# MPCBoard.net
KiCad netlist of a schematic drawn in Altium Designer
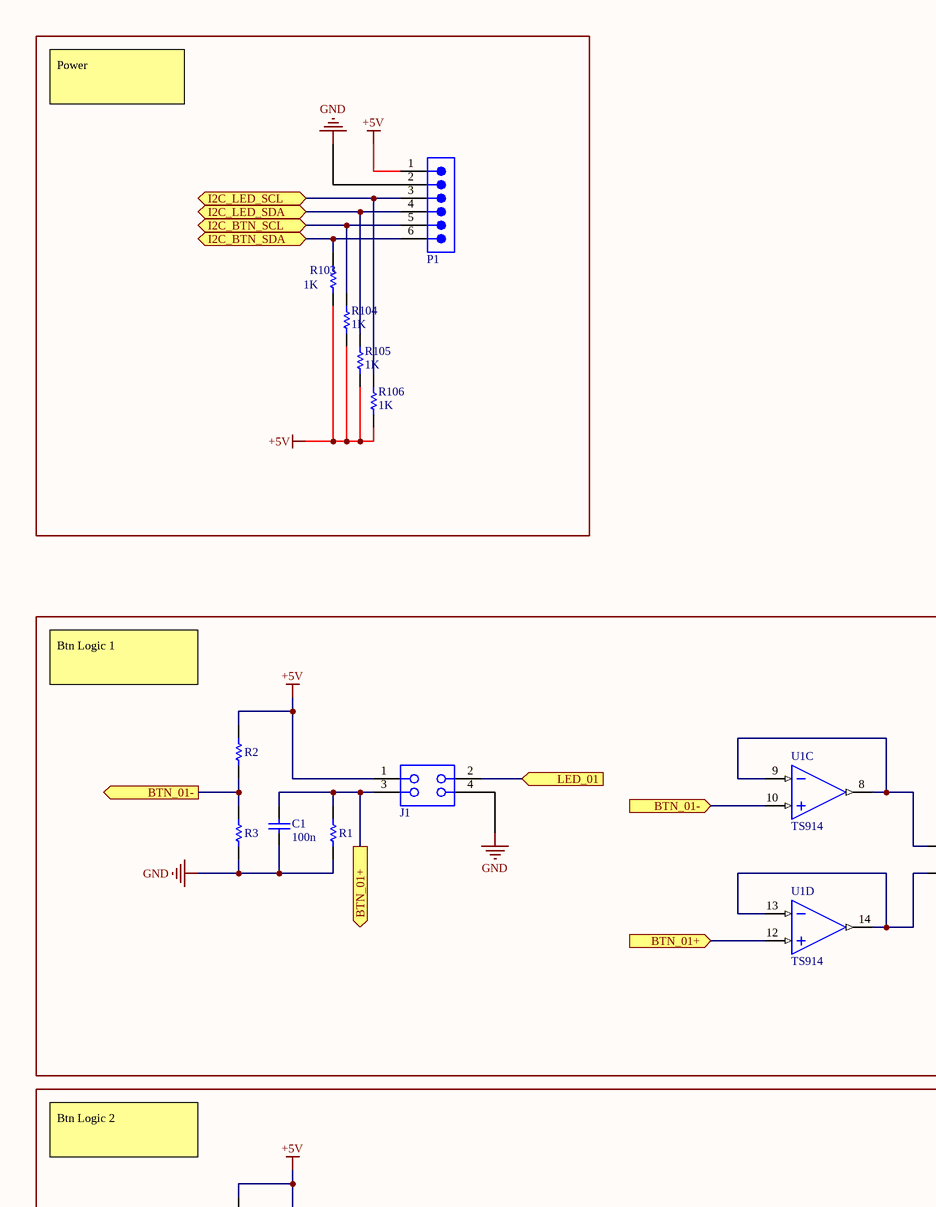
[diagram p0: MPCBoard.SchDoc, top left]
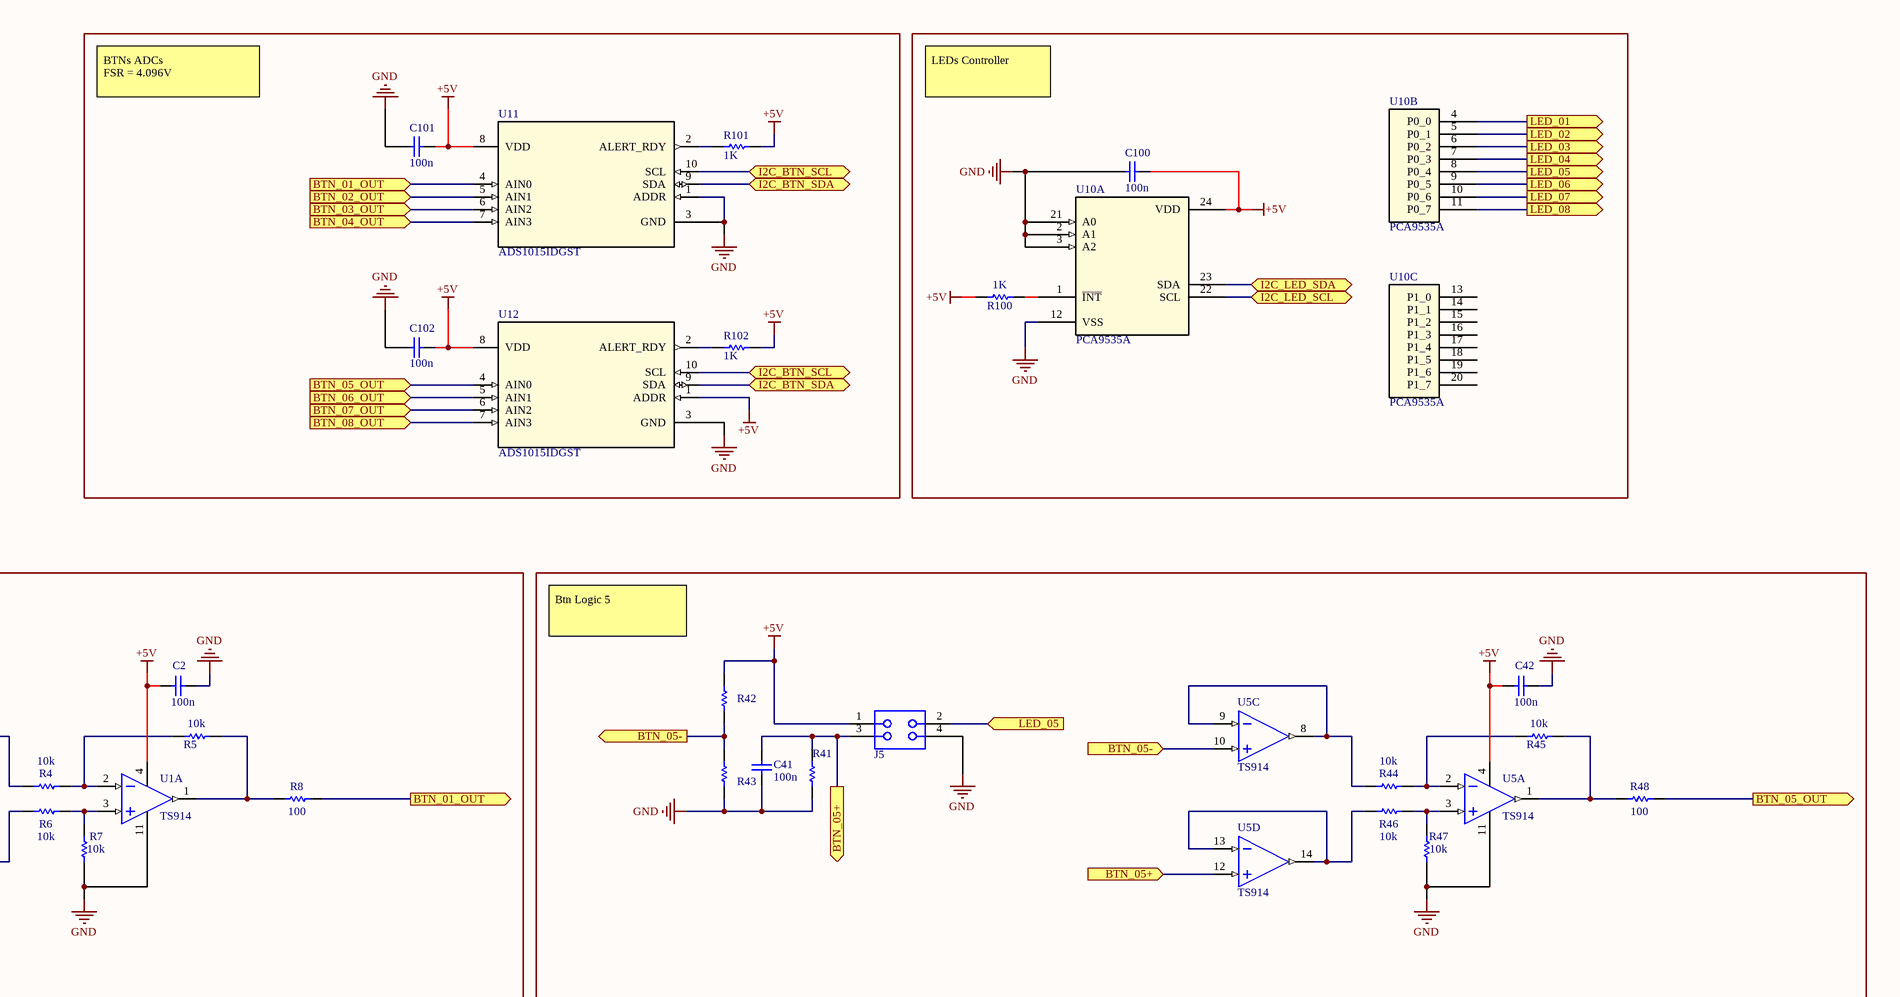
[diagram p1: MPCBoard.SchDoc, top right]
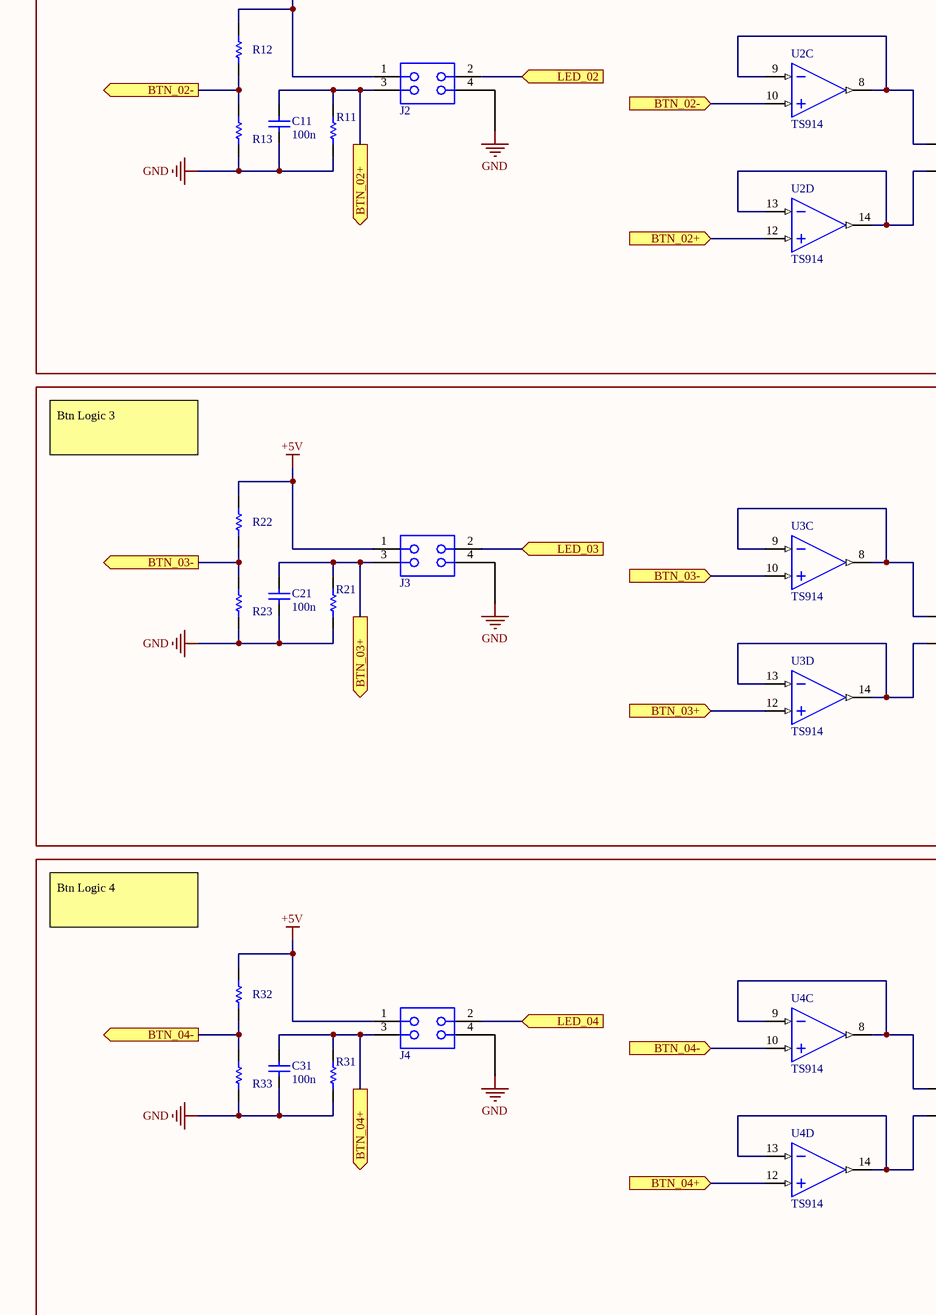
[diagram p2: MPCBoard.SchDoc, bottom left]
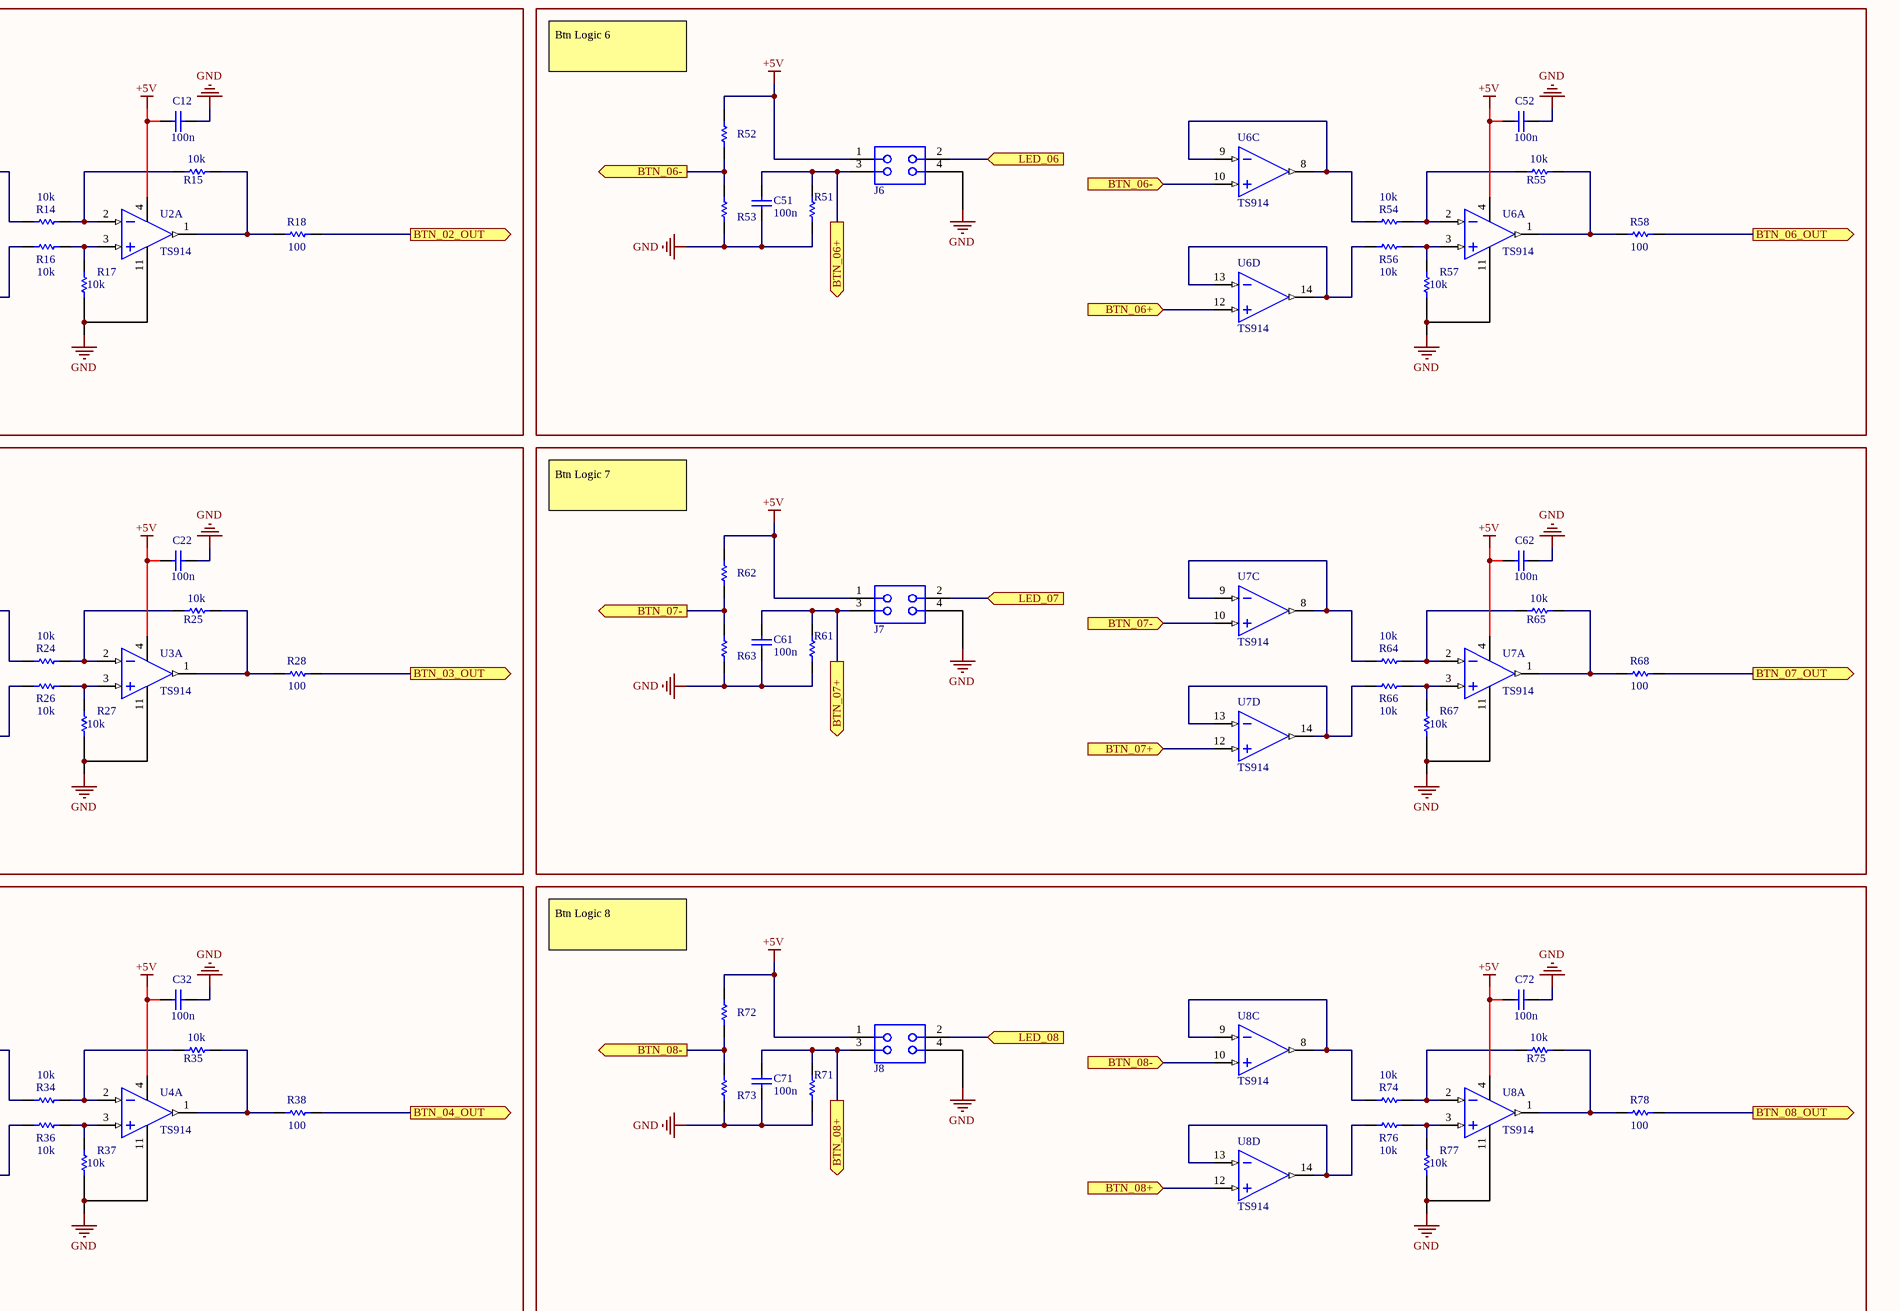
[diagram p3: MPCBoard.SchDoc, bottom right]

(export (version "E")
  (design (tool "Eeschema 10.0.6"))
  (components
    (comp (ref "C1")
      (value "100n")
      (footprint "CAPC0603(1608)100_N")
      (description "CAP")
      (libsource (lib "Passive SMD") (part "CAP"))
    )
    (comp (ref "C2")
      (value "100n")
      (footprint "CAPC0603(1608)100_N")
      (description "CAP")
      (libsource (lib "Passive SMD") (part "CAP"))
    )
    (comp (ref "C11")
      (value "100n")
      (footprint "CAPC0603(1608)100_N")
      (description "CAP")
      (libsource (lib "Passive SMD") (part "CAP"))
    )
    (comp (ref "C12")
      (value "100n")
      (footprint "CAPC0603(1608)100_N")
      (description "CAP")
      (libsource (lib "Passive SMD") (part "CAP"))
    )
    (comp (ref "C21")
      (value "100n")
      (footprint "CAPC0603(1608)100_N")
      (description "CAP")
      (libsource (lib "Passive SMD") (part "CAP"))
    )
    (comp (ref "C22")
      (value "100n")
      (footprint "CAPC0603(1608)100_N")
      (description "CAP")
      (libsource (lib "Passive SMD") (part "CAP"))
    )
    (comp (ref "C31")
      (value "100n")
      (footprint "CAPC0603(1608)100_N")
      (description "CAP")
      (libsource (lib "Passive SMD") (part "CAP"))
    )
    (comp (ref "C32")
      (value "100n")
      (footprint "CAPC0603(1608)100_N")
      (description "CAP")
      (libsource (lib "Passive SMD") (part "CAP"))
    )
    (comp (ref "C41")
      (value "100n")
      (footprint "CAPC0603(1608)100_N")
      (description "CAP")
      (libsource (lib "Passive SMD") (part "CAP"))
    )
    (comp (ref "C42")
      (value "100n")
      (footprint "CAPC0603(1608)100_N")
      (description "CAP")
      (libsource (lib "Passive SMD") (part "CAP"))
    )
    (comp (ref "C51")
      (value "100n")
      (footprint "CAPC0603(1608)100_N")
      (description "CAP")
      (libsource (lib "Passive SMD") (part "CAP"))
    )
    (comp (ref "C52")
      (value "100n")
      (footprint "CAPC0603(1608)100_N")
      (description "CAP")
      (libsource (lib "Passive SMD") (part "CAP"))
    )
    (comp (ref "C61")
      (value "100n")
      (footprint "CAPC0603(1608)100_N")
      (description "CAP")
      (libsource (lib "Passive SMD") (part "CAP"))
    )
    (comp (ref "C62")
      (value "100n")
      (footprint "CAPC0603(1608)100_N")
      (description "CAP")
      (libsource (lib "Passive SMD") (part "CAP"))
    )
    (comp (ref "C71")
      (value "100n")
      (footprint "CAPC0603(1608)100_N")
      (description "CAP")
      (libsource (lib "Passive SMD") (part "CAP"))
    )
    (comp (ref "C72")
      (value "100n")
      (footprint "CAPC0603(1608)100_N")
      (description "CAP")
      (libsource (lib "Passive SMD") (part "CAP"))
    )
    (comp (ref "C100")
      (value "100n")
      (footprint "CAPC0603(1608)100_N")
      (description "CAP")
      (libsource (lib "Passive SMD") (part "CAP"))
    )
    (comp (ref "C101")
      (value "100n")
      (footprint "CAPC0603(1608)100_N")
      (description "CAP")
      (libsource (lib "Passive SMD") (part "CAP"))
    )
    (comp (ref "C102")
      (value "100n")
      (footprint "CAPC0603(1608)100_N")
      (description "CAP")
      (libsource (lib "Passive SMD") (part "CAP"))
    )
    (comp (ref "J1")
      (value "62000421821")
      (footprint "62000421821")
      (description "WR-PHD Socket Header, THT, Vertical, pitch 2mm, 2 Row, 4P")
      (fields (field (name "MANUFACTURER") "Wurth Elektronik"))
      (libsource (lib "Wurth_WR-PHD (rev24a)") (part "62000421821"))
    )
    (comp (ref "J2")
      (value "62000421821")
      (footprint "62000421821")
      (description "WR-PHD Socket Header, THT, Vertical, pitch 2mm, 2 Row, 4P")
      (fields (field (name "MANUFACTURER") "Wurth Elektronik"))
      (libsource (lib "Wurth_WR-PHD (rev24a)") (part "62000421821"))
    )
    (comp (ref "J3")
      (value "62000421821")
      (footprint "62000421821")
      (description "WR-PHD Socket Header, THT, Vertical, pitch 2mm, 2 Row, 4P")
      (fields (field (name "MANUFACTURER") "Wurth Elektronik"))
      (libsource (lib "Wurth_WR-PHD (rev24a)") (part "62000421821"))
    )
    (comp (ref "J4")
      (value "62000421821")
      (footprint "62000421821")
      (description "WR-PHD Socket Header, THT, Vertical, pitch 2mm, 2 Row, 4P")
      (fields (field (name "MANUFACTURER") "Wurth Elektronik"))
      (libsource (lib "Wurth_WR-PHD (rev24a)") (part "62000421821"))
    )
    (comp (ref "J5")
      (value "62000421821")
      (footprint "62000421821")
      (description "WR-PHD Socket Header, THT, Vertical, pitch 2mm, 2 Row, 4P")
      (fields (field (name "MANUFACTURER") "Wurth Elektronik"))
      (libsource (lib "Wurth_WR-PHD (rev24a)") (part "62000421821"))
    )
    (comp (ref "J6")
      (value "62000421821")
      (footprint "62000421821")
      (description "WR-PHD Socket Header, THT, Vertical, pitch 2mm, 2 Row, 4P")
      (fields (field (name "MANUFACTURER") "Wurth Elektronik"))
      (libsource (lib "Wurth_WR-PHD (rev24a)") (part "62000421821"))
    )
    (comp (ref "J7")
      (value "62000421821")
      (footprint "62000421821")
      (description "WR-PHD Socket Header, THT, Vertical, pitch 2mm, 2 Row, 4P")
      (fields (field (name "MANUFACTURER") "Wurth Elektronik"))
      (libsource (lib "Wurth_WR-PHD (rev24a)") (part "62000421821"))
    )
    (comp (ref "J8")
      (value "62000421821")
      (footprint "62000421821")
      (description "WR-PHD Socket Header, THT, Vertical, pitch 2mm, 2 Row, 4P")
      (fields (field (name "MANUFACTURER") "Wurth Elektronik"))
      (libsource (lib "Wurth_WR-PHD (rev24a)") (part "62000421821"))
    )
    (comp (ref "P1")
      (value "61300611121")
      (footprint "61300611121")
      (description "WR-PHD Pin Header, THT, Vertical, pitch 2.54mm, 1 Row, 6P")
      (fields (field (name "MANUFACTURER") "Wurth Elektronik"))
      (libsource (lib "Wurth_WR-PHD (rev24a)") (part "61300611121"))
    )
    (comp (ref "R1")
      (value "RES")
      (footprint "RESC0603(1608)_N")
      (libsource (lib "Passive SMD") (part "RES"))
    )
    (comp (ref "R2")
      (value "RES")
      (footprint "RESC0603(1608)_N")
      (libsource (lib "Passive SMD") (part "RES"))
    )
    (comp (ref "R3")
      (value "RES")
      (footprint "RESC0603(1608)_N")
      (libsource (lib "Passive SMD") (part "RES"))
    )
    (comp (ref "R4")
      (value "10k")
      (footprint "RESC0603(1608)_N")
      (description "RES")
      (libsource (lib "Passive SMD") (part "RES"))
    )
    (comp (ref "R5")
      (value "10k")
      (footprint "RESC0603(1608)_N")
      (description "RES")
      (libsource (lib "Passive SMD") (part "RES"))
    )
    (comp (ref "R6")
      (value "10k")
      (footprint "RESC0603(1608)_N")
      (description "RES")
      (libsource (lib "Passive SMD") (part "RES"))
    )
    (comp (ref "R7")
      (value "10k")
      (footprint "RESC0603(1608)_N")
      (description "RES")
      (libsource (lib "Passive SMD") (part "RES"))
    )
    (comp (ref "R8")
      (value "100")
      (footprint "RESC0603(1608)_N")
      (description "RES")
      (libsource (lib "Passive SMD") (part "RES"))
    )
    (comp (ref "R11")
      (value "RES")
      (footprint "RESC0603(1608)_N")
      (libsource (lib "Passive SMD") (part "RES"))
    )
    (comp (ref "R12")
      (value "RES")
      (footprint "RESC0603(1608)_N")
      (libsource (lib "Passive SMD") (part "RES"))
    )
    (comp (ref "R13")
      (value "RES")
      (footprint "RESC0603(1608)_N")
      (libsource (lib "Passive SMD") (part "RES"))
    )
    (comp (ref "R14")
      (value "10k")
      (footprint "RESC0603(1608)_N")
      (description "RES")
      (libsource (lib "Passive SMD") (part "RES"))
    )
    (comp (ref "R15")
      (value "10k")
      (footprint "RESC0603(1608)_N")
      (description "RES")
      (libsource (lib "Passive SMD") (part "RES"))
    )
    (comp (ref "R16")
      (value "10k")
      (footprint "RESC0603(1608)_N")
      (description "RES")
      (libsource (lib "Passive SMD") (part "RES"))
    )
    (comp (ref "R17")
      (value "10k")
      (footprint "RESC0603(1608)_N")
      (description "RES")
      (libsource (lib "Passive SMD") (part "RES"))
    )
    (comp (ref "R18")
      (value "100")
      (footprint "RESC0603(1608)_N")
      (description "RES")
      (libsource (lib "Passive SMD") (part "RES"))
    )
    (comp (ref "R21")
      (value "RES")
      (footprint "RESC0603(1608)_N")
      (libsource (lib "Passive SMD") (part "RES"))
    )
    (comp (ref "R22")
      (value "RES")
      (footprint "RESC0603(1608)_N")
      (libsource (lib "Passive SMD") (part "RES"))
    )
    (comp (ref "R23")
      (value "RES")
      (footprint "RESC0603(1608)_N")
      (libsource (lib "Passive SMD") (part "RES"))
    )
    (comp (ref "R24")
      (value "10k")
      (footprint "RESC0603(1608)_N")
      (description "RES")
      (libsource (lib "Passive SMD") (part "RES"))
    )
    (comp (ref "R25")
      (value "10k")
      (footprint "RESC0603(1608)_N")
      (description "RES")
      (libsource (lib "Passive SMD") (part "RES"))
    )
    (comp (ref "R26")
      (value "10k")
      (footprint "RESC0603(1608)_N")
      (description "RES")
      (libsource (lib "Passive SMD") (part "RES"))
    )
    (comp (ref "R27")
      (value "10k")
      (footprint "RESC0603(1608)_N")
      (description "RES")
      (libsource (lib "Passive SMD") (part "RES"))
    )
    (comp (ref "R28")
      (value "100")
      (footprint "RESC0603(1608)_N")
      (description "RES")
      (libsource (lib "Passive SMD") (part "RES"))
    )
    (comp (ref "R31")
      (value "RES")
      (footprint "RESC0603(1608)_N")
      (libsource (lib "Passive SMD") (part "RES"))
    )
    (comp (ref "R32")
      (value "RES")
      (footprint "RESC0603(1608)_N")
      (libsource (lib "Passive SMD") (part "RES"))
    )
    (comp (ref "R33")
      (value "RES")
      (footprint "RESC0603(1608)_N")
      (libsource (lib "Passive SMD") (part "RES"))
    )
    (comp (ref "R34")
      (value "10k")
      (footprint "RESC0603(1608)_N")
      (description "RES")
      (libsource (lib "Passive SMD") (part "RES"))
    )
    (comp (ref "R35")
      (value "10k")
      (footprint "RESC0603(1608)_N")
      (description "RES")
      (libsource (lib "Passive SMD") (part "RES"))
    )
    (comp (ref "R36")
      (value "10k")
      (footprint "RESC0603(1608)_N")
      (description "RES")
      (libsource (lib "Passive SMD") (part "RES"))
    )
    (comp (ref "R37")
      (value "10k")
      (footprint "RESC0603(1608)_N")
      (description "RES")
      (libsource (lib "Passive SMD") (part "RES"))
    )
    (comp (ref "R38")
      (value "100")
      (footprint "RESC0603(1608)_N")
      (description "RES")
      (libsource (lib "Passive SMD") (part "RES"))
    )
    (comp (ref "R41")
      (value "RES")
      (footprint "RESC0603(1608)_N")
      (libsource (lib "Passive SMD") (part "RES"))
    )
    (comp (ref "R42")
      (value "RES")
      (footprint "RESC0603(1608)_N")
      (libsource (lib "Passive SMD") (part "RES"))
    )
    (comp (ref "R43")
      (value "RES")
      (footprint "RESC0603(1608)_N")
      (libsource (lib "Passive SMD") (part "RES"))
    )
    (comp (ref "R44")
      (value "10k")
      (footprint "RESC0603(1608)_N")
      (description "RES")
      (libsource (lib "Passive SMD") (part "RES"))
    )
    (comp (ref "R45")
      (value "10k")
      (footprint "RESC0603(1608)_N")
      (description "RES")
      (libsource (lib "Passive SMD") (part "RES"))
    )
    (comp (ref "R46")
      (value "10k")
      (footprint "RESC0603(1608)_N")
      (description "RES")
      (libsource (lib "Passive SMD") (part "RES"))
    )
    (comp (ref "R47")
      (value "10k")
      (footprint "RESC0603(1608)_N")
      (description "RES")
      (libsource (lib "Passive SMD") (part "RES"))
    )
    (comp (ref "R48")
      (value "100")
      (footprint "RESC0603(1608)_N")
      (description "RES")
      (libsource (lib "Passive SMD") (part "RES"))
    )
    (comp (ref "R51")
      (value "RES")
      (footprint "RESC0603(1608)_N")
      (libsource (lib "Passive SMD") (part "RES"))
    )
    (comp (ref "R52")
      (value "RES")
      (footprint "RESC0603(1608)_N")
      (libsource (lib "Passive SMD") (part "RES"))
    )
    (comp (ref "R53")
      (value "RES")
      (footprint "RESC0603(1608)_N")
      (libsource (lib "Passive SMD") (part "RES"))
    )
    (comp (ref "R54")
      (value "10k")
      (footprint "RESC0603(1608)_N")
      (description "RES")
      (libsource (lib "Passive SMD") (part "RES"))
    )
    (comp (ref "R55")
      (value "10k")
      (footprint "RESC0603(1608)_N")
      (description "RES")
      (libsource (lib "Passive SMD") (part "RES"))
    )
    (comp (ref "R56")
      (value "10k")
      (footprint "RESC0603(1608)_N")
      (description "RES")
      (libsource (lib "Passive SMD") (part "RES"))
    )
    (comp (ref "R57")
      (value "10k")
      (footprint "RESC0603(1608)_N")
      (description "RES")
      (libsource (lib "Passive SMD") (part "RES"))
    )
    (comp (ref "R58")
      (value "100")
      (footprint "RESC0603(1608)_N")
      (description "RES")
      (libsource (lib "Passive SMD") (part "RES"))
    )
    (comp (ref "R61")
      (value "RES")
      (footprint "RESC0603(1608)_N")
      (libsource (lib "Passive SMD") (part "RES"))
    )
    (comp (ref "R62")
      (value "RES")
      (footprint "RESC0603(1608)_N")
      (libsource (lib "Passive SMD") (part "RES"))
    )
    (comp (ref "R63")
      (value "RES")
      (footprint "RESC0603(1608)_N")
      (libsource (lib "Passive SMD") (part "RES"))
    )
    (comp (ref "R64")
      (value "10k")
      (footprint "RESC0603(1608)_N")
      (description "RES")
      (libsource (lib "Passive SMD") (part "RES"))
    )
    (comp (ref "R65")
      (value "10k")
      (footprint "RESC0603(1608)_N")
      (description "RES")
      (libsource (lib "Passive SMD") (part "RES"))
    )
    (comp (ref "R66")
      (value "10k")
      (footprint "RESC0603(1608)_N")
      (description "RES")
      (libsource (lib "Passive SMD") (part "RES"))
    )
    (comp (ref "R67")
      (value "10k")
      (footprint "RESC0603(1608)_N")
      (description "RES")
      (libsource (lib "Passive SMD") (part "RES"))
    )
    (comp (ref "R68")
      (value "100")
      (footprint "RESC0603(1608)_N")
      (description "RES")
      (libsource (lib "Passive SMD") (part "RES"))
    )
    (comp (ref "R71")
      (value "RES")
      (footprint "RESC0603(1608)_N")
      (libsource (lib "Passive SMD") (part "RES"))
    )
    (comp (ref "R72")
      (value "RES")
      (footprint "RESC0603(1608)_N")
      (libsource (lib "Passive SMD") (part "RES"))
    )
    (comp (ref "R73")
      (value "RES")
      (footprint "RESC0603(1608)_N")
      (libsource (lib "Passive SMD") (part "RES"))
    )
    (comp (ref "R74")
      (value "10k")
      (footprint "RESC0603(1608)_N")
      (description "RES")
      (libsource (lib "Passive SMD") (part "RES"))
    )
    (comp (ref "R75")
      (value "10k")
      (footprint "RESC0603(1608)_N")
      (description "RES")
      (libsource (lib "Passive SMD") (part "RES"))
    )
    (comp (ref "R76")
      (value "10k")
      (footprint "RESC0603(1608)_N")
      (description "RES")
      (libsource (lib "Passive SMD") (part "RES"))
    )
    (comp (ref "R77")
      (value "10k")
      (footprint "RESC0603(1608)_N")
      (description "RES")
      (libsource (lib "Passive SMD") (part "RES"))
    )
    (comp (ref "R78")
      (value "100")
      (footprint "RESC0603(1608)_N")
      (description "RES")
      (libsource (lib "Passive SMD") (part "RES"))
    )
    (comp (ref "R100")
      (value "1K")
      (footprint "RESC0603(1608)_N")
      (description "RES")
      (libsource (lib "Passive SMD") (part "RES"))
    )
    (comp (ref "R101")
      (value "1K")
      (footprint "RESC0603(1608)_N")
      (description "RES")
      (libsource (lib "Passive SMD") (part "RES"))
    )
    (comp (ref "R102")
      (value "1K")
      (footprint "RESC0603(1608)_N")
      (description "RES")
      (libsource (lib "Passive SMD") (part "RES"))
    )
    (comp (ref "R103")
      (value "1K")
      (footprint "RESC0603(1608)_N")
      (description "RES")
      (libsource (lib "Passive SMD") (part "RES"))
    )
    (comp (ref "R104")
      (value "1K")
      (footprint "RESC0603(1608)_N")
      (description "RES")
      (libsource (lib "Passive SMD") (part "RES"))
    )
    (comp (ref "R105")
      (value "1K")
      (footprint "RESC0603(1608)_N")
      (description "RES")
      (libsource (lib "Passive SMD") (part "RES"))
    )
    (comp (ref "R106")
      (value "1K")
      (footprint "RESC0603(1608)_N")
      (description "RES")
      (libsource (lib "Passive SMD") (part "RES"))
    )
    (comp (ref "U1") (value "TS914") (footprint "SO-14_STM") (libsource (lib "TS914AIDT") (part "TS914")))
    (comp (ref "U2") (value "TS914") (footprint "SO-14_STM") (libsource (lib "TS914AIDT") (part "TS914")))
    (comp (ref "U3") (value "TS914") (footprint "SO-14_STM") (libsource (lib "TS914AIDT") (part "TS914")))
    (comp (ref "U4") (value "TS914") (footprint "SO-14_STM") (libsource (lib "TS914AIDT") (part "TS914")))
    (comp (ref "U5") (value "TS914") (footprint "SO-14_STM") (libsource (lib "TS914AIDT") (part "TS914")))
    (comp (ref "U6") (value "TS914") (footprint "SO-14_STM") (libsource (lib "TS914AIDT") (part "TS914")))
    (comp (ref "U7") (value "TS914") (footprint "SO-14_STM") (libsource (lib "TS914AIDT") (part "TS914")))
    (comp (ref "U8") (value "TS914") (footprint "SO-14_STM") (libsource (lib "TS914AIDT") (part "TS914")))
    (comp (ref "U10")
      (value "PCA9535A")
      (footprint "TSSOP24-8N")
      (description "Low-voltage 16-bit I2C-bus I/O port with interrupt")
      (libsource (lib "NXP") (part "PCA9535A"))
    )
    (comp (ref "U11")
      (value "ADS1015IDGST")
      (footprint "DGS0010A_N")
      (fields
        (field (name "PARTNUMBER") "ADS1015IDGSR")
        (field (name "MANUFACTURER") "Texas Instruments")
        (field (name "COPYRIGHT") "Copyright (C) 2025 Ultra Librarian. All rights reserved.")
      )
      (libsource (lib "ADS1015IDGST") (part "ADS1015IDGST"))
    )
    (comp (ref "U12")
      (value "ADS1015IDGST")
      (footprint "DGS0010A_N")
      (fields
        (field (name "PARTNUMBER") "ADS1015IDGSR")
        (field (name "MANUFACTURER") "Texas Instruments")
        (field (name "COPYRIGHT") "Copyright (C) 2025 Ultra Librarian. All rights reserved.")
      )
      (libsource (lib "ADS1015IDGST") (part "ADS1015IDGST"))
    )
  )
  (nets
    (net (code "1") (name "+5V") (class "Default")
      (node (ref "C100") (pin "2") (pinfunction "2_2") (pintype "passive"))
      (node (ref "C101") (pin "2") (pinfunction "2_2") (pintype "passive"))
      (node (ref "C102") (pin "2") (pinfunction "2_2") (pintype "passive"))
      (node (ref "C12") (pin "1") (pinfunction "1_1") (pintype "passive"))
      (node (ref "C2") (pin "1") (pinfunction "1_1") (pintype "passive"))
      (node (ref "C22") (pin "1") (pinfunction "1_1") (pintype "passive"))
      (node (ref "C32") (pin "1") (pinfunction "1_1") (pintype "passive"))
      (node (ref "C42") (pin "1") (pinfunction "1_1") (pintype "passive"))
      (node (ref "C52") (pin "1") (pinfunction "1_1") (pintype "passive"))
      (node (ref "C62") (pin "1") (pinfunction "1_1") (pintype "passive"))
      (node (ref "C72") (pin "1") (pinfunction "1_1") (pintype "passive"))
      (node (ref "J1") (pin "1") (pinfunction "1_1") (pintype "passive"))
      (node (ref "J2") (pin "1") (pinfunction "1_1") (pintype "passive"))
      (node (ref "J3") (pin "1") (pinfunction "1_1") (pintype "passive"))
      (node (ref "J4") (pin "1") (pinfunction "1_1") (pintype "passive"))
      (node (ref "J5") (pin "1") (pinfunction "1_1") (pintype "passive"))
      (node (ref "J6") (pin "1") (pinfunction "1_1") (pintype "passive"))
      (node (ref "J7") (pin "1") (pinfunction "1_1") (pintype "passive"))
      (node (ref "J8") (pin "1") (pinfunction "1_1") (pintype "passive"))
      (node (ref "P1") (pin "1") (pinfunction "1_1") (pintype "passive"))
      (node (ref "R100") (pin "1") (pinfunction "1_1") (pintype "passive"))
      (node (ref "R101") (pin "1") (pinfunction "1_1") (pintype "passive"))
      (node (ref "R102") (pin "1") (pinfunction "1_1") (pintype "passive"))
      (node (ref "R103") (pin "2") (pinfunction "2_2") (pintype "passive"))
      (node (ref "R104") (pin "2") (pinfunction "2_2") (pintype "passive"))
      (node (ref "R105") (pin "2") (pinfunction "2_2") (pintype "passive"))
      (node (ref "R106") (pin "2") (pinfunction "2_2") (pintype "passive"))
      (node (ref "R12") (pin "1") (pinfunction "1_1") (pintype "passive"))
      (node (ref "R2") (pin "1") (pinfunction "1_1") (pintype "passive"))
      (node (ref "R22") (pin "1") (pinfunction "1_1") (pintype "passive"))
      (node (ref "R32") (pin "1") (pinfunction "1_1") (pintype "passive"))
      (node (ref "R42") (pin "1") (pinfunction "1_1") (pintype "passive"))
      (node (ref "R52") (pin "1") (pinfunction "1_1") (pintype "passive"))
      (node (ref "R62") (pin "1") (pinfunction "1_1") (pintype "passive"))
      (node (ref "R72") (pin "1") (pinfunction "1_1") (pintype "passive"))
      (node (ref "U1") (pin "4") (pinfunction "Vcc+_4") (pintype "power_in"))
      (node (ref "U10") (pin "24") (pinfunction "VDD_24") (pintype "power_in"))
      (node (ref "U11") (pin "8") (pinfunction "VDD_8") (pintype "power_in"))
      (node (ref "U12") (pin "1") (pinfunction "ADDR_1") (pintype "input"))
      (node (ref "U12") (pin "8") (pinfunction "VDD_8") (pintype "power_in"))
      (node (ref "U2") (pin "4") (pinfunction "Vcc+_4") (pintype "power_in"))
      (node (ref "U3") (pin "4") (pinfunction "Vcc+_4") (pintype "power_in"))
      (node (ref "U4") (pin "4") (pinfunction "Vcc+_4") (pintype "power_in"))
      (node (ref "U5") (pin "4") (pinfunction "Vcc+_4") (pintype "power_in"))
      (node (ref "U6") (pin "4") (pinfunction "Vcc+_4") (pintype "power_in"))
      (node (ref "U7") (pin "4") (pinfunction "Vcc+_4") (pintype "power_in"))
      (node (ref "U8") (pin "4") (pinfunction "Vcc+_4") (pintype "power_in"))
    )
    (net (code "2") (name "/BTN_01+") (class "Default")
      (node (ref "C1") (pin "2") (pinfunction "2_2") (pintype "passive"))
      (node (ref "J1") (pin "3") (pinfunction "3_3") (pintype "passive"))
      (node (ref "R1") (pin "1") (pinfunction "1_1") (pintype "passive"))
      (node (ref "U1") (pin "12") (pinfunction "Non-Inverting_12") (pintype "input"))
    )
    (net (code "3") (name "/BTN_01-") (class "Default")
      (node (ref "R2") (pin "2") (pinfunction "2_2") (pintype "passive"))
      (node (ref "R3") (pin "1") (pinfunction "1_1") (pintype "passive"))
      (node (ref "U1") (pin "10") (pinfunction "Non-Inverting_10") (pintype "input"))
    )
    (net (code "4") (name "/BTN_01_OUT") (class "Default")
      (node (ref "R8") (pin "1") (pinfunction "1_1") (pintype "passive"))
      (node (ref "U11") (pin "4") (pinfunction "AIN0_4") (pintype "input"))
    )
    (net (code "5") (name "/BTN_02+") (class "Default")
      (node (ref "C11") (pin "2") (pinfunction "2_2") (pintype "passive"))
      (node (ref "J2") (pin "3") (pinfunction "3_3") (pintype "passive"))
      (node (ref "R11") (pin "1") (pinfunction "1_1") (pintype "passive"))
      (node (ref "U2") (pin "12") (pinfunction "Non-Inverting_12") (pintype "input"))
    )
    (net (code "6") (name "/BTN_02-") (class "Default")
      (node (ref "R12") (pin "2") (pinfunction "2_2") (pintype "passive"))
      (node (ref "R13") (pin "1") (pinfunction "1_1") (pintype "passive"))
      (node (ref "U2") (pin "10") (pinfunction "Non-Inverting_10") (pintype "input"))
    )
    (net (code "7") (name "/BTN_02_OUT") (class "Default")
      (node (ref "R18") (pin "1") (pinfunction "1_1") (pintype "passive"))
      (node (ref "U11") (pin "5") (pinfunction "AIN1_5") (pintype "input"))
    )
    (net (code "8") (name "/BTN_03+") (class "Default")
      (node (ref "C21") (pin "2") (pinfunction "2_2") (pintype "passive"))
      (node (ref "J3") (pin "3") (pinfunction "3_3") (pintype "passive"))
      (node (ref "R21") (pin "1") (pinfunction "1_1") (pintype "passive"))
      (node (ref "U3") (pin "12") (pinfunction "Non-Inverting_12") (pintype "input"))
    )
    (net (code "9") (name "/BTN_03-") (class "Default")
      (node (ref "R22") (pin "2") (pinfunction "2_2") (pintype "passive"))
      (node (ref "R23") (pin "1") (pinfunction "1_1") (pintype "passive"))
      (node (ref "U3") (pin "10") (pinfunction "Non-Inverting_10") (pintype "input"))
    )
    (net (code "10") (name "/BTN_03_OUT") (class "Default")
      (node (ref "R28") (pin "1") (pinfunction "1_1") (pintype "passive"))
      (node (ref "U11") (pin "6") (pinfunction "AIN2_6") (pintype "input"))
    )
    (net (code "11") (name "/BTN_04+") (class "Default")
      (node (ref "C31") (pin "2") (pinfunction "2_2") (pintype "passive"))
      (node (ref "J4") (pin "3") (pinfunction "3_3") (pintype "passive"))
      (node (ref "R31") (pin "1") (pinfunction "1_1") (pintype "passive"))
      (node (ref "U4") (pin "12") (pinfunction "Non-Inverting_12") (pintype "input"))
    )
    (net (code "12") (name "/BTN_04-") (class "Default")
      (node (ref "R32") (pin "2") (pinfunction "2_2") (pintype "passive"))
      (node (ref "R33") (pin "1") (pinfunction "1_1") (pintype "passive"))
      (node (ref "U4") (pin "10") (pinfunction "Non-Inverting_10") (pintype "input"))
    )
    (net (code "13") (name "/BTN_04_OUT") (class "Default")
      (node (ref "R38") (pin "1") (pinfunction "1_1") (pintype "passive"))
      (node (ref "U11") (pin "7") (pinfunction "AIN3_7") (pintype "input"))
    )
    (net (code "14") (name "/BTN_05+") (class "Default")
      (node (ref "C41") (pin "2") (pinfunction "2_2") (pintype "passive"))
      (node (ref "J5") (pin "3") (pinfunction "3_3") (pintype "passive"))
      (node (ref "R41") (pin "1") (pinfunction "1_1") (pintype "passive"))
      (node (ref "U5") (pin "12") (pinfunction "Non-Inverting_12") (pintype "input"))
    )
    (net (code "15") (name "/BTN_05-") (class "Default")
      (node (ref "R42") (pin "2") (pinfunction "2_2") (pintype "passive"))
      (node (ref "R43") (pin "1") (pinfunction "1_1") (pintype "passive"))
      (node (ref "U5") (pin "10") (pinfunction "Non-Inverting_10") (pintype "input"))
    )
    (net (code "16") (name "/BTN_05_OUT") (class "Default")
      (node (ref "R48") (pin "1") (pinfunction "1_1") (pintype "passive"))
      (node (ref "U12") (pin "4") (pinfunction "AIN0_4") (pintype "input"))
    )
    (net (code "17") (name "/BTN_06+") (class "Default")
      (node (ref "C51") (pin "2") (pinfunction "2_2") (pintype "passive"))
      (node (ref "J6") (pin "3") (pinfunction "3_3") (pintype "passive"))
      (node (ref "R51") (pin "1") (pinfunction "1_1") (pintype "passive"))
      (node (ref "U6") (pin "12") (pinfunction "Non-Inverting_12") (pintype "input"))
    )
    (net (code "18") (name "/BTN_06-") (class "Default")
      (node (ref "R52") (pin "2") (pinfunction "2_2") (pintype "passive"))
      (node (ref "R53") (pin "1") (pinfunction "1_1") (pintype "passive"))
      (node (ref "U6") (pin "10") (pinfunction "Non-Inverting_10") (pintype "input"))
    )
    (net (code "19") (name "/BTN_06_OUT") (class "Default")
      (node (ref "R58") (pin "1") (pinfunction "1_1") (pintype "passive"))
      (node (ref "U12") (pin "5") (pinfunction "AIN1_5") (pintype "input"))
    )
    (net (code "20") (name "/BTN_07+") (class "Default")
      (node (ref "C61") (pin "2") (pinfunction "2_2") (pintype "passive"))
      (node (ref "J7") (pin "3") (pinfunction "3_3") (pintype "passive"))
      (node (ref "R61") (pin "1") (pinfunction "1_1") (pintype "passive"))
      (node (ref "U7") (pin "12") (pinfunction "Non-Inverting_12") (pintype "input"))
    )
    (net (code "21") (name "/BTN_07-") (class "Default")
      (node (ref "R62") (pin "2") (pinfunction "2_2") (pintype "passive"))
      (node (ref "R63") (pin "1") (pinfunction "1_1") (pintype "passive"))
      (node (ref "U7") (pin "10") (pinfunction "Non-Inverting_10") (pintype "input"))
    )
    (net (code "22") (name "/BTN_07_OUT") (class "Default")
      (node (ref "R68") (pin "1") (pinfunction "1_1") (pintype "passive"))
      (node (ref "U12") (pin "6") (pinfunction "AIN2_6") (pintype "input"))
    )
    (net (code "23") (name "/BTN_08+") (class "Default")
      (node (ref "C71") (pin "2") (pinfunction "2_2") (pintype "passive"))
      (node (ref "J8") (pin "3") (pinfunction "3_3") (pintype "passive"))
      (node (ref "R71") (pin "1") (pinfunction "1_1") (pintype "passive"))
      (node (ref "U8") (pin "12") (pinfunction "Non-Inverting_12") (pintype "input"))
    )
    (net (code "24") (name "/BTN_08-") (class "Default")
      (node (ref "R72") (pin "2") (pinfunction "2_2") (pintype "passive"))
      (node (ref "R73") (pin "1") (pinfunction "1_1") (pintype "passive"))
      (node (ref "U8") (pin "10") (pinfunction "Non-Inverting_10") (pintype "input"))
    )
    (net (code "25") (name "/BTN_08_OUT") (class "Default")
      (node (ref "R78") (pin "1") (pinfunction "1_1") (pintype "passive"))
      (node (ref "U12") (pin "7") (pinfunction "AIN3_7") (pintype "input"))
    )
    (net (code "26") (name "/I2C_BTN_SCL") (class "Default")
      (node (ref "P1") (pin "5") (pinfunction "5_5") (pintype "passive"))
      (node (ref "R104") (pin "1") (pinfunction "1_1") (pintype "passive"))
      (node (ref "U11") (pin "10") (pinfunction "SCL_10") (pintype "input"))
      (node (ref "U12") (pin "10") (pinfunction "SCL_10") (pintype "input"))
    )
    (net (code "27") (name "/I2C_BTN_SDA") (class "Default")
      (node (ref "P1") (pin "6") (pinfunction "6_6") (pintype "passive"))
      (node (ref "R103") (pin "1") (pinfunction "1_1") (pintype "passive"))
      (node (ref "U11") (pin "9") (pinfunction "SDA_9") (pintype "bidirectional"))
      (node (ref "U12") (pin "9") (pinfunction "SDA_9") (pintype "bidirectional"))
    )
    (net (code "28") (name "/I2C_LED_SCL") (class "Default")
      (node (ref "P1") (pin "3") (pinfunction "3_3") (pintype "passive"))
      (node (ref "R106") (pin "1") (pinfunction "1_1") (pintype "passive"))
      (node (ref "U10") (pin "22") (pinfunction "SCL_22") (pintype "passive"))
    )
    (net (code "29") (name "/I2C_LED_SDA") (class "Default")
      (node (ref "P1") (pin "4") (pinfunction "4_4") (pintype "passive"))
      (node (ref "R105") (pin "1") (pinfunction "1_1") (pintype "passive"))
      (node (ref "U10") (pin "23") (pinfunction "SDA_23") (pintype "passive"))
    )
    (net (code "30") (name "/LED_01") (class "Default")
      (node (ref "J1") (pin "2") (pinfunction "2_2") (pintype "passive"))
      (node (ref "U10") (pin "4") (pinfunction "P0_0_4") (pintype "passive"))
    )
    (net (code "31") (name "/LED_02") (class "Default")
      (node (ref "J2") (pin "2") (pinfunction "2_2") (pintype "passive"))
      (node (ref "U10") (pin "5") (pinfunction "P0_1_5") (pintype "passive"))
    )
    (net (code "32") (name "/LED_03") (class "Default")
      (node (ref "J3") (pin "2") (pinfunction "2_2") (pintype "passive"))
      (node (ref "U10") (pin "6") (pinfunction "P0_2_6") (pintype "passive"))
    )
    (net (code "33") (name "/LED_04") (class "Default")
      (node (ref "J4") (pin "2") (pinfunction "2_2") (pintype "passive"))
      (node (ref "U10") (pin "7") (pinfunction "P0_3_7") (pintype "passive"))
    )
    (net (code "34") (name "/LED_05") (class "Default")
      (node (ref "J5") (pin "2") (pinfunction "2_2") (pintype "passive"))
      (node (ref "U10") (pin "8") (pinfunction "P0_4_8") (pintype "passive"))
    )
    (net (code "35") (name "/LED_06") (class "Default")
      (node (ref "J6") (pin "2") (pinfunction "2_2") (pintype "passive"))
      (node (ref "U10") (pin "9") (pinfunction "P0_5_9") (pintype "passive"))
    )
    (net (code "36") (name "/LED_07") (class "Default")
      (node (ref "J7") (pin "2") (pinfunction "2_2") (pintype "passive"))
      (node (ref "U10") (pin "10") (pinfunction "P0_6_10") (pintype "passive"))
    )
    (net (code "37") (name "/LED_08") (class "Default")
      (node (ref "J8") (pin "2") (pinfunction "2_2") (pintype "passive"))
      (node (ref "U10") (pin "11") (pinfunction "P0_7_11") (pintype "passive"))
    )
    (net (code "38") (name "GND") (class "Default")
      (node (ref "C1") (pin "1") (pinfunction "1_1") (pintype "passive"))
      (node (ref "C100") (pin "1") (pinfunction "1_1") (pintype "passive"))
      (node (ref "C101") (pin "1") (pinfunction "1_1") (pintype "passive"))
      (node (ref "C102") (pin "1") (pinfunction "1_1") (pintype "passive"))
      (node (ref "C11") (pin "1") (pinfunction "1_1") (pintype "passive"))
      (node (ref "C12") (pin "2") (pinfunction "2_2") (pintype "passive"))
      (node (ref "C2") (pin "2") (pinfunction "2_2") (pintype "passive"))
      (node (ref "C21") (pin "1") (pinfunction "1_1") (pintype "passive"))
      (node (ref "C22") (pin "2") (pinfunction "2_2") (pintype "passive"))
      (node (ref "C31") (pin "1") (pinfunction "1_1") (pintype "passive"))
      (node (ref "C32") (pin "2") (pinfunction "2_2") (pintype "passive"))
      (node (ref "C41") (pin "1") (pinfunction "1_1") (pintype "passive"))
      (node (ref "C42") (pin "2") (pinfunction "2_2") (pintype "passive"))
      (node (ref "C51") (pin "1") (pinfunction "1_1") (pintype "passive"))
      (node (ref "C52") (pin "2") (pinfunction "2_2") (pintype "passive"))
      (node (ref "C61") (pin "1") (pinfunction "1_1") (pintype "passive"))
      (node (ref "C62") (pin "2") (pinfunction "2_2") (pintype "passive"))
      (node (ref "C71") (pin "1") (pinfunction "1_1") (pintype "passive"))
      (node (ref "C72") (pin "2") (pinfunction "2_2") (pintype "passive"))
      (node (ref "J1") (pin "4") (pinfunction "4_4") (pintype "passive"))
      (node (ref "J2") (pin "4") (pinfunction "4_4") (pintype "passive"))
      (node (ref "J3") (pin "4") (pinfunction "4_4") (pintype "passive"))
      (node (ref "J4") (pin "4") (pinfunction "4_4") (pintype "passive"))
      (node (ref "J5") (pin "4") (pinfunction "4_4") (pintype "passive"))
      (node (ref "J6") (pin "4") (pinfunction "4_4") (pintype "passive"))
      (node (ref "J7") (pin "4") (pinfunction "4_4") (pintype "passive"))
      (node (ref "J8") (pin "4") (pinfunction "4_4") (pintype "passive"))
      (node (ref "P1") (pin "2") (pinfunction "2_2") (pintype "passive"))
      (node (ref "R1") (pin "2") (pinfunction "2_2") (pintype "passive"))
      (node (ref "R11") (pin "2") (pinfunction "2_2") (pintype "passive"))
      (node (ref "R13") (pin "2") (pinfunction "2_2") (pintype "passive"))
      (node (ref "R17") (pin "1") (pinfunction "1_1") (pintype "passive"))
      (node (ref "R21") (pin "2") (pinfunction "2_2") (pintype "passive"))
      (node (ref "R23") (pin "2") (pinfunction "2_2") (pintype "passive"))
      (node (ref "R27") (pin "1") (pinfunction "1_1") (pintype "passive"))
      (node (ref "R3") (pin "2") (pinfunction "2_2") (pintype "passive"))
      (node (ref "R31") (pin "2") (pinfunction "2_2") (pintype "passive"))
      (node (ref "R33") (pin "2") (pinfunction "2_2") (pintype "passive"))
      (node (ref "R37") (pin "1") (pinfunction "1_1") (pintype "passive"))
      (node (ref "R41") (pin "2") (pinfunction "2_2") (pintype "passive"))
      (node (ref "R43") (pin "2") (pinfunction "2_2") (pintype "passive"))
      (node (ref "R47") (pin "1") (pinfunction "1_1") (pintype "passive"))
      (node (ref "R51") (pin "2") (pinfunction "2_2") (pintype "passive"))
      (node (ref "R53") (pin "2") (pinfunction "2_2") (pintype "passive"))
      (node (ref "R57") (pin "1") (pinfunction "1_1") (pintype "passive"))
      (node (ref "R61") (pin "2") (pinfunction "2_2") (pintype "passive"))
      (node (ref "R63") (pin "2") (pinfunction "2_2") (pintype "passive"))
      (node (ref "R67") (pin "1") (pinfunction "1_1") (pintype "passive"))
      (node (ref "R7") (pin "1") (pinfunction "1_1") (pintype "passive"))
      (node (ref "R71") (pin "2") (pinfunction "2_2") (pintype "passive"))
      (node (ref "R73") (pin "2") (pinfunction "2_2") (pintype "passive"))
      (node (ref "R77") (pin "1") (pinfunction "1_1") (pintype "passive"))
      (node (ref "U1") (pin "11") (pinfunction "Vcc-_11") (pintype "power_in"))
      (node (ref "U10") (pin "12") (pinfunction "VSS_12") (pintype "power_in"))
      (node (ref "U10") (pin "2") (pinfunction "A1_2") (pintype "input"))
      (node (ref "U10") (pin "21") (pinfunction "A0_21") (pintype "input"))
      (node (ref "U10") (pin "3") (pinfunction "A2_3") (pintype "input"))
      (node (ref "U11") (pin "1") (pinfunction "ADDR_1") (pintype "input"))
      (node (ref "U11") (pin "3") (pinfunction "GND_3") (pintype "power_in"))
      (node (ref "U12") (pin "3") (pinfunction "GND_3") (pintype "power_in"))
      (node (ref "U2") (pin "11") (pinfunction "Vcc-_11") (pintype "power_in"))
      (node (ref "U3") (pin "11") (pinfunction "Vcc-_11") (pintype "power_in"))
      (node (ref "U4") (pin "11") (pinfunction "Vcc-_11") (pintype "power_in"))
      (node (ref "U5") (pin "11") (pinfunction "Vcc-_11") (pintype "power_in"))
      (node (ref "U6") (pin "11") (pinfunction "Vcc-_11") (pintype "power_in"))
      (node (ref "U7") (pin "11") (pinfunction "Vcc-_11") (pintype "power_in"))
      (node (ref "U8") (pin "11") (pinfunction "Vcc-_11") (pintype "power_in"))
    )
    (net (code "39") (name "Net-(U1A-Inverting)") (class "Default")
      (node (ref "R4") (pin "2") (pinfunction "2_2") (pintype "passive"))
      (node (ref "R5") (pin "2") (pinfunction "2_2") (pintype "passive"))
      (node (ref "U1") (pin "2") (pinfunction "Inverting_2") (pintype "input"))
    )
    (net (code "40") (name "Net-(U1A-Non-Inverting)") (class "Default")
      (node (ref "R6") (pin "2") (pinfunction "2_2") (pintype "passive"))
      (node (ref "R7") (pin "2") (pinfunction "2_2") (pintype "passive"))
      (node (ref "U1") (pin "3") (pinfunction "Non-Inverting_3") (pintype "input"))
    )
    (net (code "41") (name "Net-(U1A-Output)") (class "Default")
      (node (ref "R5") (pin "1") (pinfunction "1_1") (pintype "passive"))
      (node (ref "R8") (pin "2") (pinfunction "2_2") (pintype "passive"))
      (node (ref "U1") (pin "1") (pinfunction "Output_1") (pintype "output"))
    )
    (net (code "42") (name "Net-(U1C-Inverting)") (class "Default")
      (node (ref "R4") (pin "1") (pinfunction "1_1") (pintype "passive"))
      (node (ref "U1") (pin "8") (pinfunction "Output_8") (pintype "output"))
      (node (ref "U1") (pin "9") (pinfunction "Inverting_9") (pintype "input"))
    )
    (net (code "43") (name "Net-(U1D-Inverting)") (class "Default")
      (node (ref "R6") (pin "1") (pinfunction "1_1") (pintype "passive"))
      (node (ref "U1") (pin "13") (pinfunction "Inverting_13") (pintype "input"))
      (node (ref "U1") (pin "14") (pinfunction "Output_14") (pintype "output"))
    )
    (net (code "44") (name "Net-(U2A-Inverting)") (class "Default")
      (node (ref "R14") (pin "2") (pinfunction "2_2") (pintype "passive"))
      (node (ref "R15") (pin "2") (pinfunction "2_2") (pintype "passive"))
      (node (ref "U2") (pin "2") (pinfunction "Inverting_2") (pintype "input"))
    )
    (net (code "45") (name "Net-(U2A-Non-Inverting)") (class "Default")
      (node (ref "R16") (pin "2") (pinfunction "2_2") (pintype "passive"))
      (node (ref "R17") (pin "2") (pinfunction "2_2") (pintype "passive"))
      (node (ref "U2") (pin "3") (pinfunction "Non-Inverting_3") (pintype "input"))
    )
    (net (code "46") (name "Net-(U2A-Output)") (class "Default")
      (node (ref "R15") (pin "1") (pinfunction "1_1") (pintype "passive"))
      (node (ref "R18") (pin "2") (pinfunction "2_2") (pintype "passive"))
      (node (ref "U2") (pin "1") (pinfunction "Output_1") (pintype "output"))
    )
    (net (code "47") (name "Net-(U2C-Inverting)") (class "Default")
      (node (ref "R14") (pin "1") (pinfunction "1_1") (pintype "passive"))
      (node (ref "U2") (pin "8") (pinfunction "Output_8") (pintype "output"))
      (node (ref "U2") (pin "9") (pinfunction "Inverting_9") (pintype "input"))
    )
    (net (code "48") (name "Net-(U2D-Inverting)") (class "Default")
      (node (ref "R16") (pin "1") (pinfunction "1_1") (pintype "passive"))
      (node (ref "U2") (pin "13") (pinfunction "Inverting_13") (pintype "input"))
      (node (ref "U2") (pin "14") (pinfunction "Output_14") (pintype "output"))
    )
    (net (code "49") (name "Net-(U3A-Inverting)") (class "Default")
      (node (ref "R24") (pin "2") (pinfunction "2_2") (pintype "passive"))
      (node (ref "R25") (pin "2") (pinfunction "2_2") (pintype "passive"))
      (node (ref "U3") (pin "2") (pinfunction "Inverting_2") (pintype "input"))
    )
    (net (code "50") (name "Net-(U3A-Non-Inverting)") (class "Default")
      (node (ref "R26") (pin "2") (pinfunction "2_2") (pintype "passive"))
      (node (ref "R27") (pin "2") (pinfunction "2_2") (pintype "passive"))
      (node (ref "U3") (pin "3") (pinfunction "Non-Inverting_3") (pintype "input"))
    )
    (net (code "51") (name "Net-(U3A-Output)") (class "Default")
      (node (ref "R25") (pin "1") (pinfunction "1_1") (pintype "passive"))
      (node (ref "R28") (pin "2") (pinfunction "2_2") (pintype "passive"))
      (node (ref "U3") (pin "1") (pinfunction "Output_1") (pintype "output"))
    )
    (net (code "52") (name "Net-(U3C-Inverting)") (class "Default")
      (node (ref "R24") (pin "1") (pinfunction "1_1") (pintype "passive"))
      (node (ref "U3") (pin "8") (pinfunction "Output_8") (pintype "output"))
      (node (ref "U3") (pin "9") (pinfunction "Inverting_9") (pintype "input"))
    )
    (net (code "53") (name "Net-(U3D-Inverting)") (class "Default")
      (node (ref "R26") (pin "1") (pinfunction "1_1") (pintype "passive"))
      (node (ref "U3") (pin "13") (pinfunction "Inverting_13") (pintype "input"))
      (node (ref "U3") (pin "14") (pinfunction "Output_14") (pintype "output"))
    )
    (net (code "54") (name "Net-(U4A-Inverting)") (class "Default")
      (node (ref "R34") (pin "2") (pinfunction "2_2") (pintype "passive"))
      (node (ref "R35") (pin "2") (pinfunction "2_2") (pintype "passive"))
      (node (ref "U4") (pin "2") (pinfunction "Inverting_2") (pintype "input"))
    )
    (net (code "55") (name "Net-(U4A-Non-Inverting)") (class "Default")
      (node (ref "R36") (pin "2") (pinfunction "2_2") (pintype "passive"))
      (node (ref "R37") (pin "2") (pinfunction "2_2") (pintype "passive"))
      (node (ref "U4") (pin "3") (pinfunction "Non-Inverting_3") (pintype "input"))
    )
    (net (code "56") (name "Net-(U4A-Output)") (class "Default")
      (node (ref "R35") (pin "1") (pinfunction "1_1") (pintype "passive"))
      (node (ref "R38") (pin "2") (pinfunction "2_2") (pintype "passive"))
      (node (ref "U4") (pin "1") (pinfunction "Output_1") (pintype "output"))
    )
    (net (code "57") (name "Net-(U4C-Inverting)") (class "Default")
      (node (ref "R34") (pin "1") (pinfunction "1_1") (pintype "passive"))
      (node (ref "U4") (pin "8") (pinfunction "Output_8") (pintype "output"))
      (node (ref "U4") (pin "9") (pinfunction "Inverting_9") (pintype "input"))
    )
    (net (code "58") (name "Net-(U4D-Inverting)") (class "Default")
      (node (ref "R36") (pin "1") (pinfunction "1_1") (pintype "passive"))
      (node (ref "U4") (pin "13") (pinfunction "Inverting_13") (pintype "input"))
      (node (ref "U4") (pin "14") (pinfunction "Output_14") (pintype "output"))
    )
    (net (code "59") (name "Net-(U5A-Inverting)") (class "Default")
      (node (ref "R44") (pin "2") (pinfunction "2_2") (pintype "passive"))
      (node (ref "R45") (pin "2") (pinfunction "2_2") (pintype "passive"))
      (node (ref "U5") (pin "2") (pinfunction "Inverting_2") (pintype "input"))
    )
    (net (code "60") (name "Net-(U5A-Non-Inverting)") (class "Default")
      (node (ref "R46") (pin "2") (pinfunction "2_2") (pintype "passive"))
      (node (ref "R47") (pin "2") (pinfunction "2_2") (pintype "passive"))
      (node (ref "U5") (pin "3") (pinfunction "Non-Inverting_3") (pintype "input"))
    )
    (net (code "61") (name "Net-(U5A-Output)") (class "Default")
      (node (ref "R45") (pin "1") (pinfunction "1_1") (pintype "passive"))
      (node (ref "R48") (pin "2") (pinfunction "2_2") (pintype "passive"))
      (node (ref "U5") (pin "1") (pinfunction "Output_1") (pintype "output"))
    )
    (net (code "62") (name "Net-(U5C-Inverting)") (class "Default")
      (node (ref "R44") (pin "1") (pinfunction "1_1") (pintype "passive"))
      (node (ref "U5") (pin "8") (pinfunction "Output_8") (pintype "output"))
      (node (ref "U5") (pin "9") (pinfunction "Inverting_9") (pintype "input"))
    )
    (net (code "63") (name "Net-(U5D-Inverting)") (class "Default")
      (node (ref "R46") (pin "1") (pinfunction "1_1") (pintype "passive"))
      (node (ref "U5") (pin "13") (pinfunction "Inverting_13") (pintype "input"))
      (node (ref "U5") (pin "14") (pinfunction "Output_14") (pintype "output"))
    )
    (net (code "64") (name "Net-(U6A-Inverting)") (class "Default")
      (node (ref "R54") (pin "2") (pinfunction "2_2") (pintype "passive"))
      (node (ref "R55") (pin "2") (pinfunction "2_2") (pintype "passive"))
      (node (ref "U6") (pin "2") (pinfunction "Inverting_2") (pintype "input"))
    )
    (net (code "65") (name "Net-(U6A-Non-Inverting)") (class "Default")
      (node (ref "R56") (pin "2") (pinfunction "2_2") (pintype "passive"))
      (node (ref "R57") (pin "2") (pinfunction "2_2") (pintype "passive"))
      (node (ref "U6") (pin "3") (pinfunction "Non-Inverting_3") (pintype "input"))
    )
    (net (code "66") (name "Net-(U6A-Output)") (class "Default")
      (node (ref "R55") (pin "1") (pinfunction "1_1") (pintype "passive"))
      (node (ref "R58") (pin "2") (pinfunction "2_2") (pintype "passive"))
      (node (ref "U6") (pin "1") (pinfunction "Output_1") (pintype "output"))
    )
    (net (code "67") (name "Net-(U6C-Inverting)") (class "Default")
      (node (ref "R54") (pin "1") (pinfunction "1_1") (pintype "passive"))
      (node (ref "U6") (pin "8") (pinfunction "Output_8") (pintype "output"))
      (node (ref "U6") (pin "9") (pinfunction "Inverting_9") (pintype "input"))
    )
    (net (code "68") (name "Net-(U6D-Inverting)") (class "Default")
      (node (ref "R56") (pin "1") (pinfunction "1_1") (pintype "passive"))
      (node (ref "U6") (pin "13") (pinfunction "Inverting_13") (pintype "input"))
      (node (ref "U6") (pin "14") (pinfunction "Output_14") (pintype "output"))
    )
    (net (code "69") (name "Net-(U7A-Inverting)") (class "Default")
      (node (ref "R64") (pin "2") (pinfunction "2_2") (pintype "passive"))
      (node (ref "R65") (pin "2") (pinfunction "2_2") (pintype "passive"))
      (node (ref "U7") (pin "2") (pinfunction "Inverting_2") (pintype "input"))
    )
    (net (code "70") (name "Net-(U7A-Non-Inverting)") (class "Default")
      (node (ref "R66") (pin "2") (pinfunction "2_2") (pintype "passive"))
      (node (ref "R67") (pin "2") (pinfunction "2_2") (pintype "passive"))
      (node (ref "U7") (pin "3") (pinfunction "Non-Inverting_3") (pintype "input"))
    )
    (net (code "71") (name "Net-(U7A-Output)") (class "Default")
      (node (ref "R65") (pin "1") (pinfunction "1_1") (pintype "passive"))
      (node (ref "R68") (pin "2") (pinfunction "2_2") (pintype "passive"))
      (node (ref "U7") (pin "1") (pinfunction "Output_1") (pintype "output"))
    )
    (net (code "72") (name "Net-(U7C-Inverting)") (class "Default")
      (node (ref "R64") (pin "1") (pinfunction "1_1") (pintype "passive"))
      (node (ref "U7") (pin "8") (pinfunction "Output_8") (pintype "output"))
      (node (ref "U7") (pin "9") (pinfunction "Inverting_9") (pintype "input"))
    )
    (net (code "73") (name "Net-(U7D-Inverting)") (class "Default")
      (node (ref "R66") (pin "1") (pinfunction "1_1") (pintype "passive"))
      (node (ref "U7") (pin "13") (pinfunction "Inverting_13") (pintype "input"))
      (node (ref "U7") (pin "14") (pinfunction "Output_14") (pintype "output"))
    )
    (net (code "74") (name "Net-(U8A-Inverting)") (class "Default")
      (node (ref "R74") (pin "2") (pinfunction "2_2") (pintype "passive"))
      (node (ref "R75") (pin "2") (pinfunction "2_2") (pintype "passive"))
      (node (ref "U8") (pin "2") (pinfunction "Inverting_2") (pintype "input"))
    )
    (net (code "75") (name "Net-(U8A-Non-Inverting)") (class "Default")
      (node (ref "R76") (pin "2") (pinfunction "2_2") (pintype "passive"))
      (node (ref "R77") (pin "2") (pinfunction "2_2") (pintype "passive"))
      (node (ref "U8") (pin "3") (pinfunction "Non-Inverting_3") (pintype "input"))
    )
    (net (code "76") (name "Net-(U8A-Output)") (class "Default")
      (node (ref "R75") (pin "1") (pinfunction "1_1") (pintype "passive"))
      (node (ref "R78") (pin "2") (pinfunction "2_2") (pintype "passive"))
      (node (ref "U8") (pin "1") (pinfunction "Output_1") (pintype "output"))
    )
    (net (code "77") (name "Net-(U8C-Inverting)") (class "Default")
      (node (ref "R74") (pin "1") (pinfunction "1_1") (pintype "passive"))
      (node (ref "U8") (pin "8") (pinfunction "Output_8") (pintype "output"))
      (node (ref "U8") (pin "9") (pinfunction "Inverting_9") (pintype "input"))
    )
    (net (code "78") (name "Net-(U8D-Inverting)") (class "Default")
      (node (ref "R76") (pin "1") (pinfunction "1_1") (pintype "passive"))
      (node (ref "U8") (pin "13") (pinfunction "Inverting_13") (pintype "input"))
      (node (ref "U8") (pin "14") (pinfunction "Output_14") (pintype "output"))
    )
    (net (code "79") (name "Net-(U10A-~{INT})") (class "Default")
      (node (ref "R100") (pin "2") (pinfunction "2_2") (pintype "passive"))
      (node (ref "U10") (pin "1") (pinfunction "~{INT}_1") (pintype "open_collector"))
    )
    (net (code "80") (name "Net-(U11-ALERT_RDY)") (class "Default")
      (node (ref "R101") (pin "2") (pinfunction "2_2") (pintype "passive"))
      (node (ref "U11") (pin "2") (pinfunction "ALERT_RDY_2") (pintype "output"))
    )
    (net (code "81") (name "Net-(U12-ALERT_RDY)") (class "Default")
      (node (ref "R102") (pin "2") (pinfunction "2_2") (pintype "passive"))
      (node (ref "U12") (pin "2") (pinfunction "ALERT_RDY_2") (pintype "output"))
    )
    (net (code "82") (name "unconnected-(U10C-P1_0-Pad13)") (class "Default")
      (node (ref "U10") (pin "13") (pinfunction "P1_0_13") (pintype "passive"))
    )
    (net (code "83") (name "unconnected-(U10C-P1_1-Pad14)") (class "Default")
      (node (ref "U10") (pin "14") (pinfunction "P1_1_14") (pintype "passive"))
    )
    (net (code "84") (name "unconnected-(U10C-P1_2-Pad15)") (class "Default")
      (node (ref "U10") (pin "15") (pinfunction "P1_2_15") (pintype "passive"))
    )
    (net (code "85") (name "unconnected-(U10C-P1_3-Pad16)") (class "Default")
      (node (ref "U10") (pin "16") (pinfunction "P1_3_16") (pintype "passive"))
    )
    (net (code "86") (name "unconnected-(U10C-P1_4-Pad17)") (class "Default")
      (node (ref "U10") (pin "17") (pinfunction "P1_4_17") (pintype "passive"))
    )
    (net (code "87") (name "unconnected-(U10C-P1_5-Pad18)") (class "Default")
      (node (ref "U10") (pin "18") (pinfunction "P1_5_18") (pintype "passive"))
    )
    (net (code "88") (name "unconnected-(U10C-P1_6-Pad19)") (class "Default")
      (node (ref "U10") (pin "19") (pinfunction "P1_6_19") (pintype "passive"))
    )
    (net (code "89") (name "unconnected-(U10C-P1_7-Pad20)") (class "Default")
      (node (ref "U10") (pin "20") (pinfunction "P1_7_20") (pintype "passive"))
    )
  )
)
